# Radio_Module_2.net
KiCad netlist of a schematic drawn in EAGLE
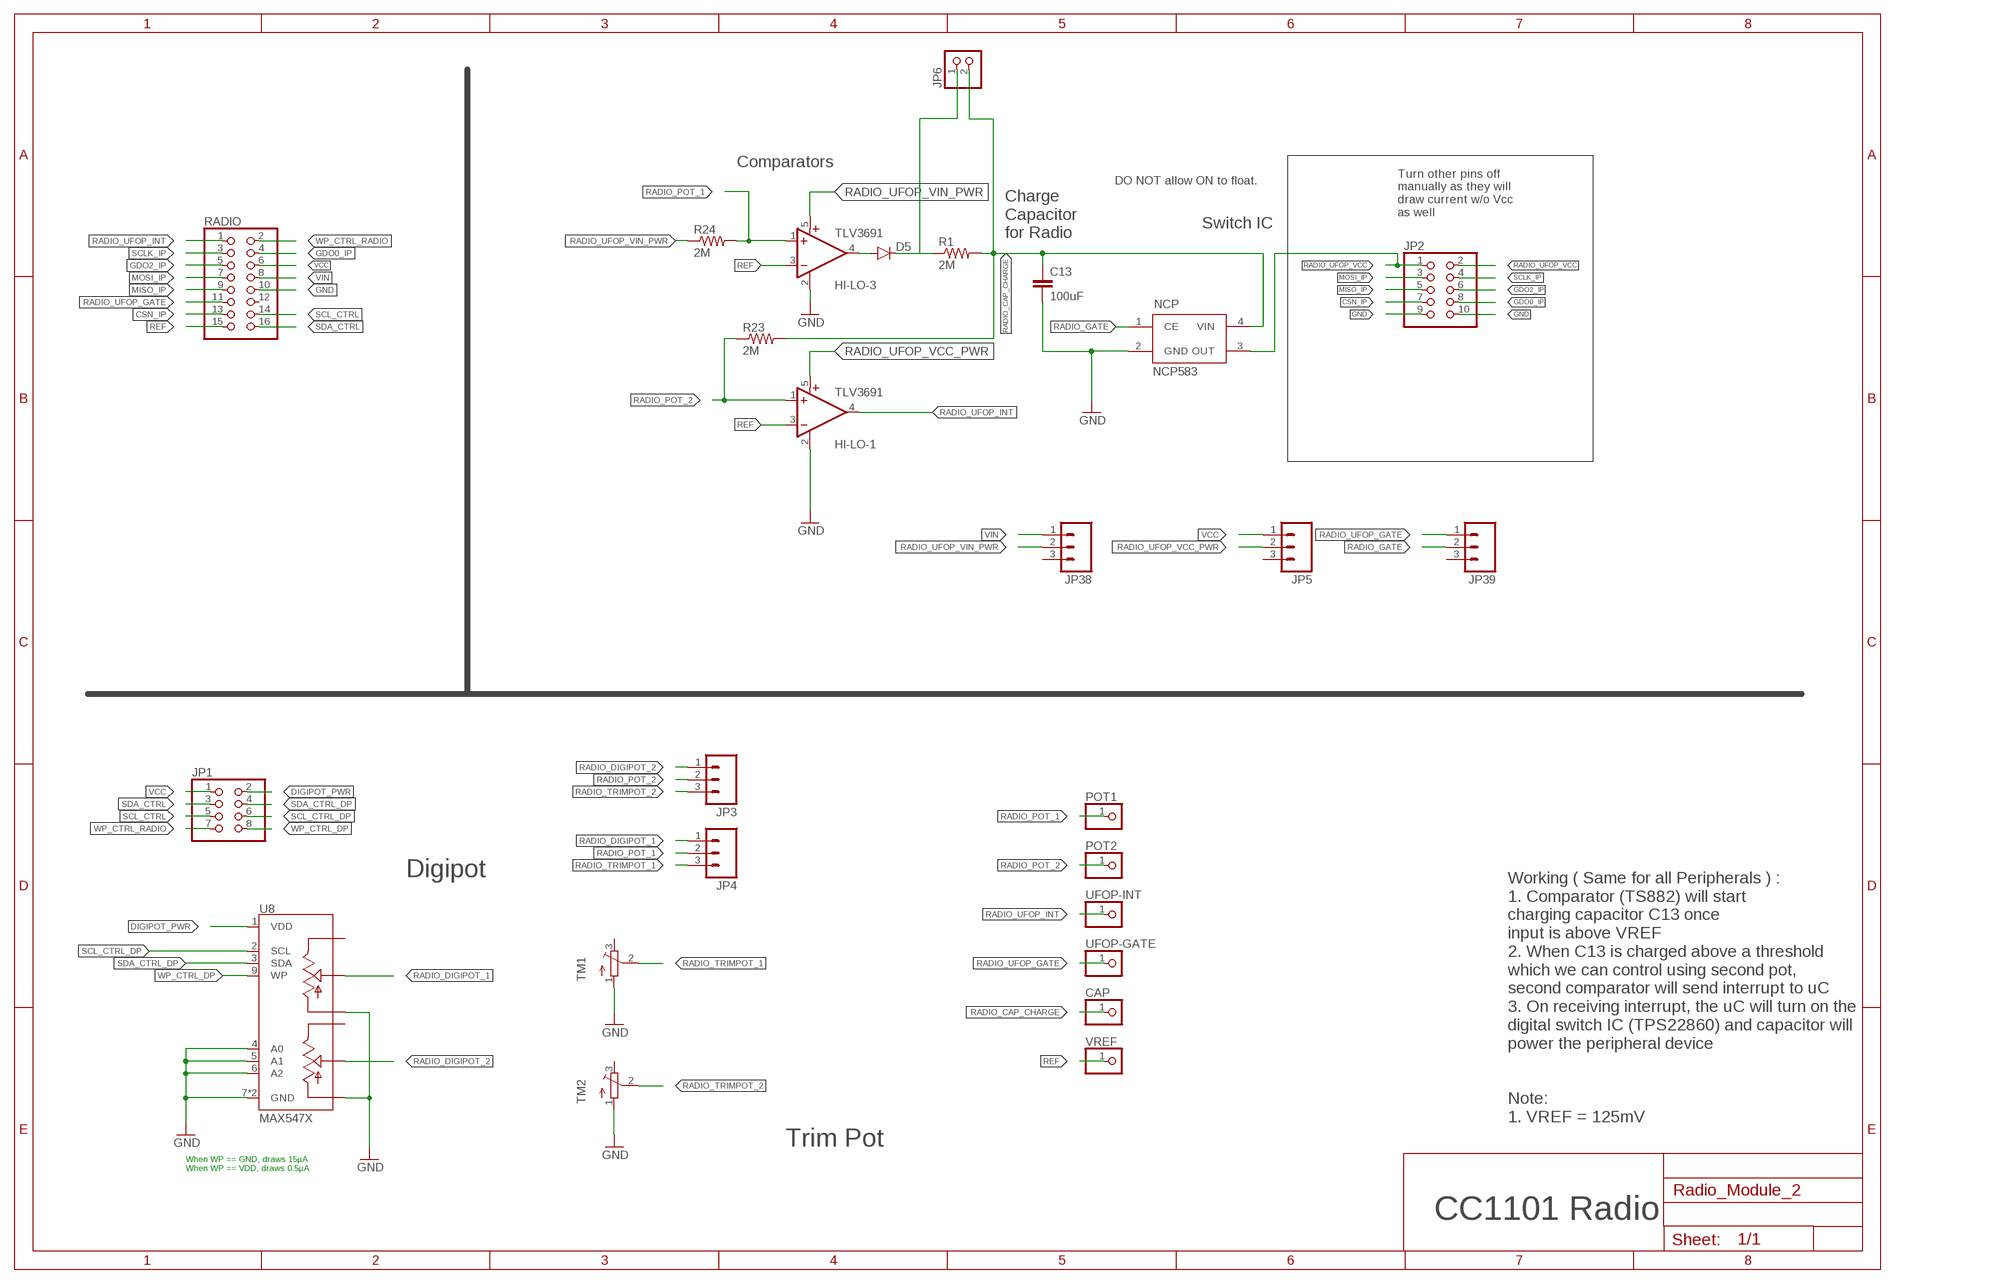
[diagram p0: schematic, sheet 1]

(export (version "E")
  (design (tool "Eeschema 10.0.6"))
  (components
    (comp (ref "C13")
      (value "100uF")
      (footprint "eagle-import:0805")
      (libsource (lib "eagle-import") (part "CAP0805"))
    )
    (comp (ref "CAP")
      (value "PINHD-1X1")
      (footprint "eagle-import:1X01")
      (libsource (lib "eagle-import") (part "PINHD-1X1"))
    )
    (comp (ref "D5")
      (value "DIODESOD523")
      (footprint "eagle-import:SOD523")
      (libsource (lib "eagle-import") (part "DIODESOD523"))
    )
    (comp (ref "HI-LO-1")
      (value "TLV3691")
      (footprint "eagle-import:SC70-5")
      (libsource (lib "eagle-import") (part "TLV3691"))
    )
    (comp (ref "HI-LO-3")
      (value "TLV3691")
      (footprint "eagle-import:SC70-5")
      (libsource (lib "eagle-import") (part "TLV3691"))
    )
    (comp (ref "JP1")
      (value "PINHD-2X4")
      (footprint "eagle-import:2X04")
      (libsource (lib "eagle-import") (part "PINHD-2X4"))
    )
    (comp (ref "JP2")
      (value "PINHD-2X5")
      (footprint "eagle-import:2X05")
      (libsource (lib "eagle-import") (part "PINHD-2X5"))
    )
    (comp (ref "JP3")
      (value "M03")
      (footprint "eagle-import:1X03-1.27MM")
      (libsource (lib "eagle-import") (part "M03"))
    )
    (comp (ref "JP4")
      (value "M03")
      (footprint "eagle-import:1X03-1.27MM")
      (libsource (lib "eagle-import") (part "M03"))
    )
    (comp (ref "JP5")
      (value "M03")
      (footprint "eagle-import:1X03-1.27MM")
      (libsource (lib "eagle-import") (part "M03"))
    )
    (comp (ref "JP6")
      (value "PINHD-1X2")
      (footprint "eagle-import:1X02")
      (libsource (lib "eagle-import") (part "PINHD-1X2"))
    )
    (comp (ref "JP38")
      (value "M03")
      (footprint "eagle-import:1X03-1.27MM")
      (libsource (lib "eagle-import") (part "M03"))
    )
    (comp (ref "JP39")
      (value "M03")
      (footprint "eagle-import:1X03-1.27MM")
      (libsource (lib "eagle-import") (part "M03"))
    )
    (comp (ref "NCP")
      (value "NCP583")
      (footprint "eagle-import:SC82-AB_1PRIMARY")
      (libsource (lib "eagle-import") (part "NCP583"))
    )
    (comp (ref "POT1")
      (value "PINHD-1X1")
      (footprint "eagle-import:1X01")
      (libsource (lib "eagle-import") (part "PINHD-1X1"))
    )
    (comp (ref "POT2")
      (value "PINHD-1X1")
      (footprint "eagle-import:1X01")
      (libsource (lib "eagle-import") (part "PINHD-1X1"))
    )
    (comp (ref "R1")
      (value "2M")
      (footprint "eagle-import:0805")
      (libsource (lib "eagle-import") (part "RESISTOR0805-RES"))
    )
    (comp (ref "R23")
      (value "2M")
      (footprint "eagle-import:0805")
      (libsource (lib "eagle-import") (part "RESISTOR0805-RES"))
    )
    (comp (ref "R24")
      (value "2M")
      (footprint "eagle-import:0805")
      (libsource (lib "eagle-import") (part "RESISTOR0805-RES"))
    )
    (comp (ref "RADIO")
      (value "PINHD-2X8/90")
      (footprint "eagle-import:2X08_90")
      (libsource (lib "eagle-import") (part "PINHD-2X8/90"))
    )
    (comp (ref "TM1")
      (value "TRIMPOTTC33X")
      (footprint "eagle-import:TC33X")
      (libsource (lib "eagle-import") (part "TRIMPOTTC33X"))
    )
    (comp (ref "TM2")
      (value "TRIMPOTTC33X")
      (footprint "eagle-import:TC33X")
      (libsource (lib "eagle-import") (part "TRIMPOTTC33X"))
    )
    (comp (ref "U8")
      (value "MAX547X")
      (footprint "eagle-import:QFN16")
      (libsource (lib "eagle-import") (part "MAX547X"))
    )
    (comp (ref "UFOP-GATE")
      (value "PINHD-1X1")
      (footprint "eagle-import:1X01")
      (libsource (lib "eagle-import") (part "PINHD-1X1"))
    )
    (comp (ref "UFOP-INT")
      (value "PINHD-1X1")
      (footprint "eagle-import:1X01")
      (libsource (lib "eagle-import") (part "PINHD-1X1"))
    )
    (comp (ref "VREF")
      (value "PINHD-1X1")
      (footprint "eagle-import:1X01")
      (libsource (lib "eagle-import") (part "PINHD-1X1"))
    )
  )
  (nets
    (net (code "1") (name "CSN_IP") (class "Default")
      (node (ref "JP2") (pin "7") (pinfunction "7_7") (pintype "passive"))
      (node (ref "RADIO") (pin "13") (pinfunction "13_13") (pintype "passive"))
    )
    (net (code "2") (name "DIGIPOT_PWR") (class "Default")
      (node (ref "JP1") (pin "2") (pinfunction "2_2") (pintype "passive"))
      (node (ref "U8") (pin "1") (pinfunction "VDD_1") (pintype "bidirectional"))
    )
    (net (code "3") (name "GDO0_IP") (class "Default")
      (node (ref "JP2") (pin "8") (pinfunction "8_8") (pintype "passive"))
      (node (ref "RADIO") (pin "4") (pinfunction "4_4") (pintype "passive"))
    )
    (net (code "4") (name "GDO2_IP") (class "Default")
      (node (ref "JP2") (pin "6") (pinfunction "6_6") (pintype "passive"))
      (node (ref "RADIO") (pin "5") (pinfunction "5_5") (pintype "passive"))
    )
    (net (code "5") (name "GND") (class "Default")
      (node (ref "C13") (pin "2") (pinfunction "2_2") (pintype "passive"))
      (node (ref "HI-LO-1") (pin "2") (pinfunction "GND_2") (pintype "power_in"))
      (node (ref "HI-LO-3") (pin "2") (pinfunction "GND_2") (pintype "power_in"))
      (node (ref "JP2") (pin "10") (pinfunction "10_10") (pintype "passive"))
      (node (ref "JP2") (pin "9") (pinfunction "9_9") (pintype "passive"))
      (node (ref "NCP") (pin "2") (pinfunction "GND_2") (pintype "bidirectional"))
      (node (ref "RADIO") (pin "10") (pinfunction "10_10") (pintype "passive"))
      (node (ref "TM1") (pin "1") (pinfunction "A_1") (pintype "passive"))
      (node (ref "TM2") (pin "1") (pinfunction "A_1") (pintype "passive"))
      (node (ref "U8") (pin "10") (pinfunction "LB_10") (pintype "bidirectional"))
      (node (ref "U8") (pin "13") (pinfunction "LA_13") (pintype "passive"))
      (node (ref "U8") (pin "4") (pinfunction "A0_4") (pintype "bidirectional"))
      (node (ref "U8") (pin "5") (pinfunction "A1_5") (pintype "bidirectional"))
      (node (ref "U8") (pin "6") (pinfunction "A2_6") (pintype "bidirectional"))
      (node (ref "U8") (pin "7") (pinfunction "GND_7") (pintype "bidirectional"))
      (node (ref "U8") (pin "TH") (pinfunction "GND_TH") (pintype "bidirectional"))
    )
    (net (code "6") (name "MISO_IP") (class "Default")
      (node (ref "JP2") (pin "5") (pinfunction "5_5") (pintype "passive"))
      (node (ref "RADIO") (pin "9") (pinfunction "9_9") (pintype "passive"))
    )
    (net (code "7") (name "MOSI_IP") (class "Default")
      (node (ref "JP2") (pin "3") (pinfunction "3_3") (pintype "passive"))
      (node (ref "RADIO") (pin "7") (pinfunction "7_7") (pintype "passive"))
    )
    (net (code "8") (name "Net-(D5-PadC)") (class "Default")
      (node (ref "D5") (pin "C") (pinfunction "C_C") (pintype "passive"))
      (node (ref "JP6") (pin "1") (pinfunction "1_1") (pintype "passive"))
      (node (ref "R1") (pin "1") (pinfunction "1_1") (pintype "passive"))
    )
    (net (code "9") (name "Net-(HI-LO-3-OUT)") (class "Default")
      (node (ref "D5") (pin "A") (pinfunction "A_A") (pintype "passive"))
      (node (ref "HI-LO-3") (pin "4") (pinfunction "OUT_4") (pintype "output"))
    )
    (net (code "10") (name "RADIO_CAP_CHARGE") (class "Default")
      (node (ref "C13") (pin "1") (pinfunction "1_1") (pintype "passive"))
      (node (ref "CAP") (pin "1") (pinfunction "1_1") (pintype "passive"))
      (node (ref "JP6") (pin "2") (pinfunction "2_2") (pintype "passive"))
      (node (ref "NCP") (pin "4") (pinfunction "VIN_4") (pintype "bidirectional"))
      (node (ref "R1") (pin "2") (pinfunction "2_2") (pintype "passive"))
      (node (ref "R23") (pin "2") (pinfunction "2_2") (pintype "passive"))
    )
    (net (code "11") (name "RADIO_DIGIPOT_1") (class "Default")
      (node (ref "JP4") (pin "1") (pinfunction "1_1") (pintype "passive"))
      (node (ref "U8") (pin "14") (pinfunction "WA_14") (pintype "passive"))
    )
    (net (code "12") (name "RADIO_DIGIPOT_2") (class "Default")
      (node (ref "JP3") (pin "1") (pinfunction "1_1") (pintype "passive"))
      (node (ref "U8") (pin "11") (pinfunction "WB_11") (pintype "bidirectional"))
    )
    (net (code "13") (name "RADIO_GATE") (class "Default")
      (node (ref "JP39") (pin "2") (pinfunction "2_2") (pintype "passive"))
      (node (ref "NCP") (pin "1") (pinfunction "CE_1") (pintype "bidirectional"))
    )
    (net (code "14") (name "RADIO_POT_1") (class "Default")
      (node (ref "HI-LO-3") (pin "1") (pinfunction "+IN_1") (pintype "input"))
      (node (ref "JP4") (pin "2") (pinfunction "2_2") (pintype "passive"))
      (node (ref "POT1") (pin "1") (pinfunction "1_1") (pintype "passive"))
      (node (ref "R24") (pin "2") (pinfunction "2_2") (pintype "passive"))
    )
    (net (code "15") (name "RADIO_POT_2") (class "Default")
      (node (ref "HI-LO-1") (pin "1") (pinfunction "+IN_1") (pintype "input"))
      (node (ref "JP3") (pin "2") (pinfunction "2_2") (pintype "passive"))
      (node (ref "POT2") (pin "1") (pinfunction "1_1") (pintype "passive"))
      (node (ref "R23") (pin "1") (pinfunction "1_1") (pintype "passive"))
    )
    (net (code "16") (name "RADIO_TRIMPOT_1") (class "Default")
      (node (ref "JP4") (pin "3") (pinfunction "3_3") (pintype "passive"))
      (node (ref "TM1") (pin "2") (pinfunction "S_2") (pintype "passive"))
    )
    (net (code "17") (name "RADIO_TRIMPOT_2") (class "Default")
      (node (ref "JP3") (pin "3") (pinfunction "3_3") (pintype "passive"))
      (node (ref "TM2") (pin "2") (pinfunction "S_2") (pintype "passive"))
    )
    (net (code "18") (name "RADIO_UFOP_GATE") (class "Default")
      (node (ref "JP39") (pin "1") (pinfunction "1_1") (pintype "passive"))
      (node (ref "RADIO") (pin "11") (pinfunction "11_11") (pintype "passive"))
      (node (ref "UFOP-GATE") (pin "1") (pinfunction "1_1") (pintype "passive"))
    )
    (net (code "19") (name "RADIO_UFOP_INT") (class "Default")
      (node (ref "HI-LO-1") (pin "4") (pinfunction "OUT_4") (pintype "output"))
      (node (ref "RADIO") (pin "1") (pinfunction "1_1") (pintype "passive"))
      (node (ref "UFOP-INT") (pin "1") (pinfunction "1_1") (pintype "passive"))
    )
    (net (code "20") (name "RADIO_UFOP_VCC") (class "Default")
      (node (ref "JP2") (pin "1") (pinfunction "1_1") (pintype "passive"))
      (node (ref "JP2") (pin "2") (pinfunction "2_2") (pintype "passive"))
      (node (ref "NCP") (pin "3") (pinfunction "OUT_3") (pintype "bidirectional"))
    )
    (net (code "21") (name "RADIO_UFOP_VCC_PWR") (class "Default")
      (node (ref "HI-LO-1") (pin "5") (pinfunction "V+_5") (pintype "power_in"))
      (node (ref "JP5") (pin "2") (pinfunction "2_2") (pintype "passive"))
    )
    (net (code "22") (name "RADIO_UFOP_VIN_PWR") (class "Default")
      (node (ref "HI-LO-3") (pin "5") (pinfunction "V+_5") (pintype "power_in"))
      (node (ref "JP38") (pin "2") (pinfunction "2_2") (pintype "passive"))
      (node (ref "R24") (pin "1") (pinfunction "1_1") (pintype "passive"))
    )
    (net (code "23") (name "REF") (class "Default")
      (node (ref "HI-LO-1") (pin "3") (pinfunction "-IN_3") (pintype "input"))
      (node (ref "HI-LO-3") (pin "3") (pinfunction "-IN_3") (pintype "input"))
      (node (ref "RADIO") (pin "15") (pinfunction "15_15") (pintype "passive"))
      (node (ref "VREF") (pin "1") (pinfunction "1_1") (pintype "passive"))
    )
    (net (code "24") (name "SCLK_IP") (class "Default")
      (node (ref "JP2") (pin "4") (pinfunction "4_4") (pintype "passive"))
      (node (ref "RADIO") (pin "3") (pinfunction "3_3") (pintype "passive"))
    )
    (net (code "25") (name "SCL_CTRL") (class "Default")
      (node (ref "JP1") (pin "5") (pinfunction "5_5") (pintype "passive"))
      (node (ref "RADIO") (pin "14") (pinfunction "14_14") (pintype "passive"))
    )
    (net (code "26") (name "SCL_CTRL_DP") (class "Default")
      (node (ref "JP1") (pin "6") (pinfunction "6_6") (pintype "passive"))
      (node (ref "U8") (pin "2") (pinfunction "SCL_2") (pintype "bidirectional"))
    )
    (net (code "27") (name "SDA_CTRL") (class "Default")
      (node (ref "JP1") (pin "3") (pinfunction "3_3") (pintype "passive"))
      (node (ref "RADIO") (pin "16") (pinfunction "16_16") (pintype "passive"))
    )
    (net (code "28") (name "SDA_CTRL_DP") (class "Default")
      (node (ref "JP1") (pin "4") (pinfunction "4_4") (pintype "passive"))
      (node (ref "U8") (pin "3") (pinfunction "SDA_3") (pintype "bidirectional"))
    )
    (net (code "29") (name "VCC") (class "Default")
      (node (ref "JP1") (pin "1") (pinfunction "1_1") (pintype "passive"))
      (node (ref "JP5") (pin "1") (pinfunction "1_1") (pintype "passive"))
      (node (ref "RADIO") (pin "6") (pinfunction "6_6") (pintype "passive"))
    )
    (net (code "30") (name "VIN") (class "Default")
      (node (ref "JP38") (pin "1") (pinfunction "1_1") (pintype "passive"))
      (node (ref "RADIO") (pin "8") (pinfunction "8_8") (pintype "passive"))
    )
    (net (code "31") (name "WP_CTRL_DP") (class "Default")
      (node (ref "JP1") (pin "8") (pinfunction "8_8") (pintype "passive"))
      (node (ref "U8") (pin "9") (pinfunction "WP_9") (pintype "bidirectional"))
    )
    (net (code "32") (name "WP_CTRL_RADIO") (class "Default")
      (node (ref "JP1") (pin "7") (pinfunction "7_7") (pintype "passive"))
      (node (ref "RADIO") (pin "2") (pinfunction "2_2") (pintype "passive"))
    )
    (net (code "33") (name "unconnected-(JP5-Pad3)") (class "Default")
      (node (ref "JP5") (pin "3") (pinfunction "3_3") (pintype "passive"))
    )
    (net (code "34") (name "unconnected-(JP38-Pad3)") (class "Default")
      (node (ref "JP38") (pin "3") (pinfunction "3_3") (pintype "passive"))
    )
    (net (code "35") (name "unconnected-(JP39-Pad3)") (class "Default")
      (node (ref "JP39") (pin "3") (pinfunction "3_3") (pintype "passive"))
    )
    (net (code "36") (name "unconnected-(RADIO-Pad12)") (class "Default")
      (node (ref "RADIO") (pin "12") (pinfunction "12_12") (pintype "passive"))
    )
    (net (code "37") (name "unconnected-(TM1-E-Pad3)") (class "Default")
      (node (ref "TM1") (pin "3") (pinfunction "E_3") (pintype "passive"))
    )
    (net (code "38") (name "unconnected-(TM2-E-Pad3)") (class "Default")
      (node (ref "TM2") (pin "3") (pinfunction "E_3") (pintype "passive"))
    )
    (net (code "39") (name "unconnected-(U8-HA-Pad15)") (class "Default")
      (node (ref "U8") (pin "15") (pinfunction "HA_15") (pintype "passive"))
    )
    (net (code "40") (name "unconnected-(U8-HB-Pad12)") (class "Default")
      (node (ref "U8") (pin "12") (pinfunction "HB_12") (pintype "bidirectional"))
    )
  )
)
